# connectors.net
KiCad netlist of a schematic drawn in Altium Designer
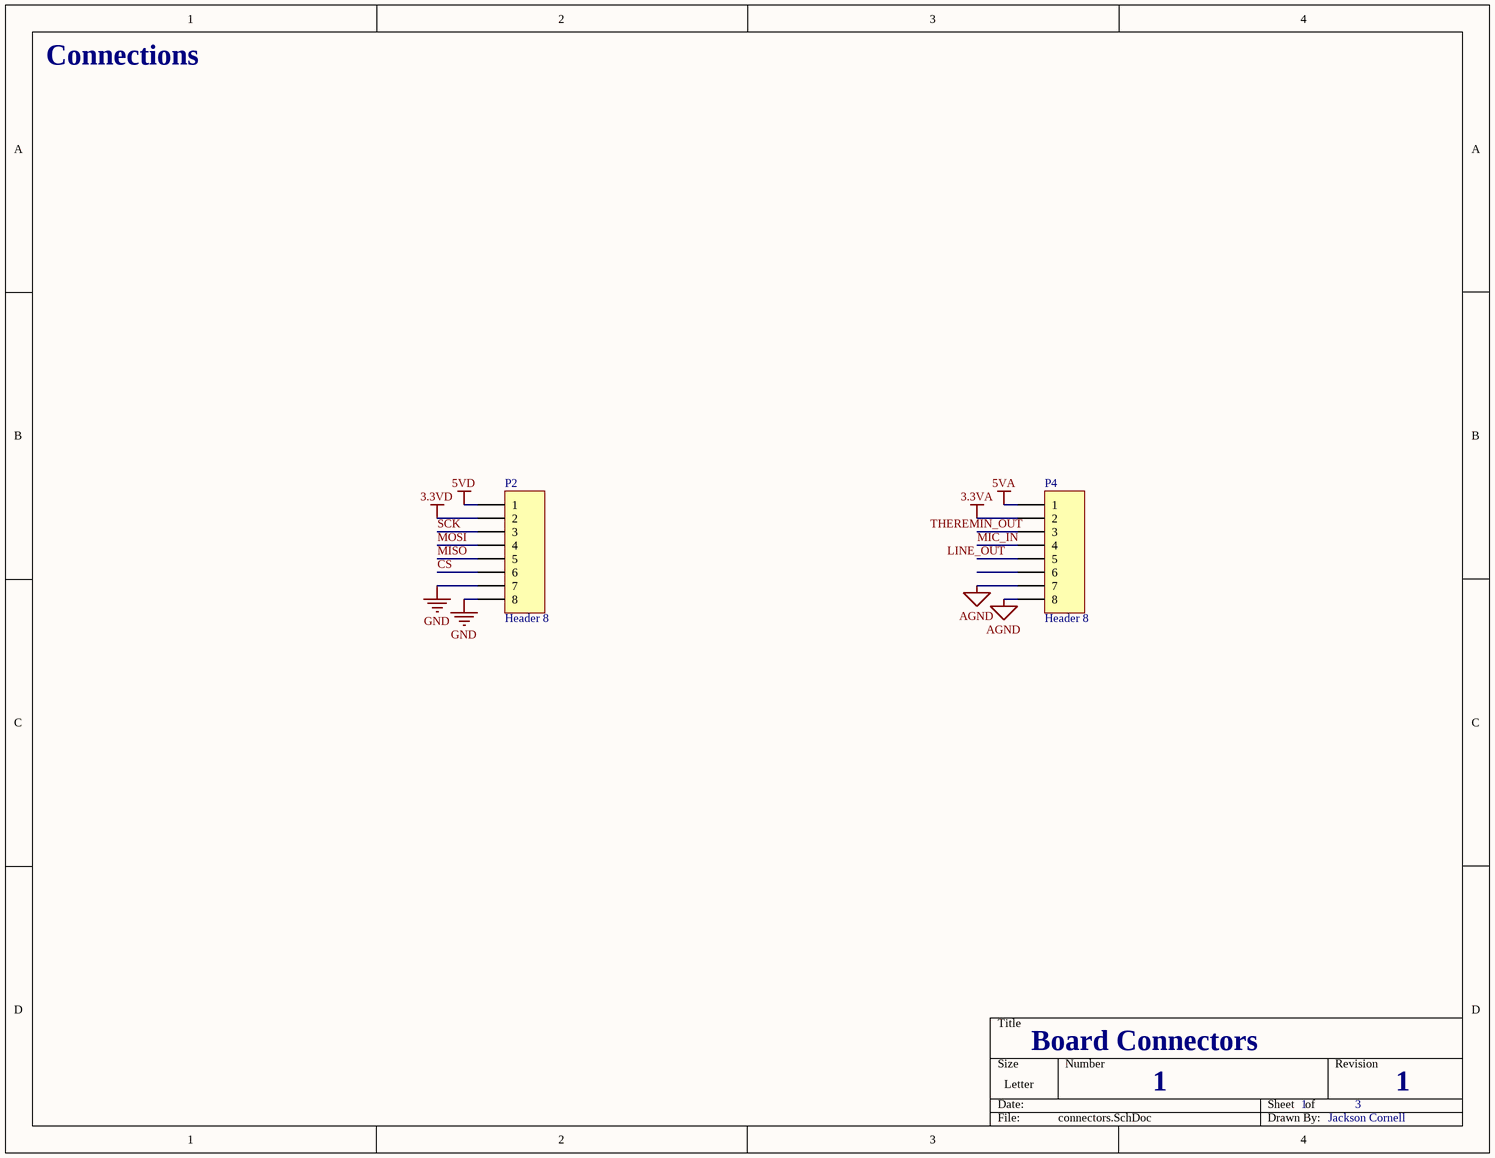
[diagram p0: connectors.SchDoc]

(export (version "E")
  (design (tool "Eeschema 10.0.6"))
  (components
    (comp (ref "P2")
      (value "Header 8")
      (footprint "HDR1X8")
      (description "Header, 8-Pin")
      (fields (field (name "PUBLISHER") "Altium Limited"))
      (libsource (lib "Miscellaneous Connectors") (part "Header 8"))
    )
    (comp (ref "P4")
      (value "Header 8")
      (footprint "HDR1X8")
      (description "Header, 8-Pin")
      (fields (field (name "PUBLISHER") "Altium Limited"))
      (libsource (lib "Miscellaneous Connectors") (part "Header 8"))
    )
  )
  (nets
    (net (code "1") (name "/CS") (class "Default")
      (node (ref "P2") (pin "6") (pinfunction "6_6") (pintype "passive"))
    )
    (net (code "2") (name "/LINE_OUT") (class "Default")
      (node (ref "P4") (pin "5") (pinfunction "5_5") (pintype "passive"))
    )
    (net (code "3") (name "/MIC_IN") (class "Default")
      (node (ref "P4") (pin "4") (pinfunction "4_4") (pintype "passive"))
    )
    (net (code "4") (name "/MISO") (class "Default")
      (node (ref "P2") (pin "5") (pinfunction "5_5") (pintype "passive"))
    )
    (net (code "5") (name "/MOSI") (class "Default")
      (node (ref "P2") (pin "4") (pinfunction "4_4") (pintype "passive"))
    )
    (net (code "6") (name "/SCK") (class "Default")
      (node (ref "P2") (pin "3") (pinfunction "3_3") (pintype "passive"))
    )
    (net (code "7") (name "/THEREMIN_OUT") (class "Default")
      (node (ref "P4") (pin "3") (pinfunction "3_3") (pintype "passive"))
    )
    (net (code "8") (name "3.3VA") (class "Default")
      (node (ref "P4") (pin "2") (pinfunction "2_2") (pintype "passive"))
    )
    (net (code "9") (name "3.3VD") (class "Default")
      (node (ref "P2") (pin "2") (pinfunction "2_2") (pintype "passive"))
    )
    (net (code "10") (name "5VA") (class "Default")
      (node (ref "P4") (pin "1") (pinfunction "1_1") (pintype "passive"))
    )
    (net (code "11") (name "5VD") (class "Default")
      (node (ref "P2") (pin "1") (pinfunction "1_1") (pintype "passive"))
    )
    (net (code "12") (name "AGND") (class "Default")
      (node (ref "P4") (pin "7") (pinfunction "7_7") (pintype "passive"))
      (node (ref "P4") (pin "8") (pinfunction "8_8") (pintype "passive"))
    )
    (net (code "13") (name "GND") (class "Default")
      (node (ref "P2") (pin "7") (pinfunction "7_7") (pintype "passive"))
      (node (ref "P2") (pin "8") (pinfunction "8_8") (pintype "passive"))
    )
    (net (code "14") (name "unconnected-(P4-Pad6)") (class "Default")
      (node (ref "P4") (pin "6") (pinfunction "6_6") (pintype "passive"))
    )
  )
)
